# Mataric1.net
KiCad netlist of a schematic drawn in Altium Designer
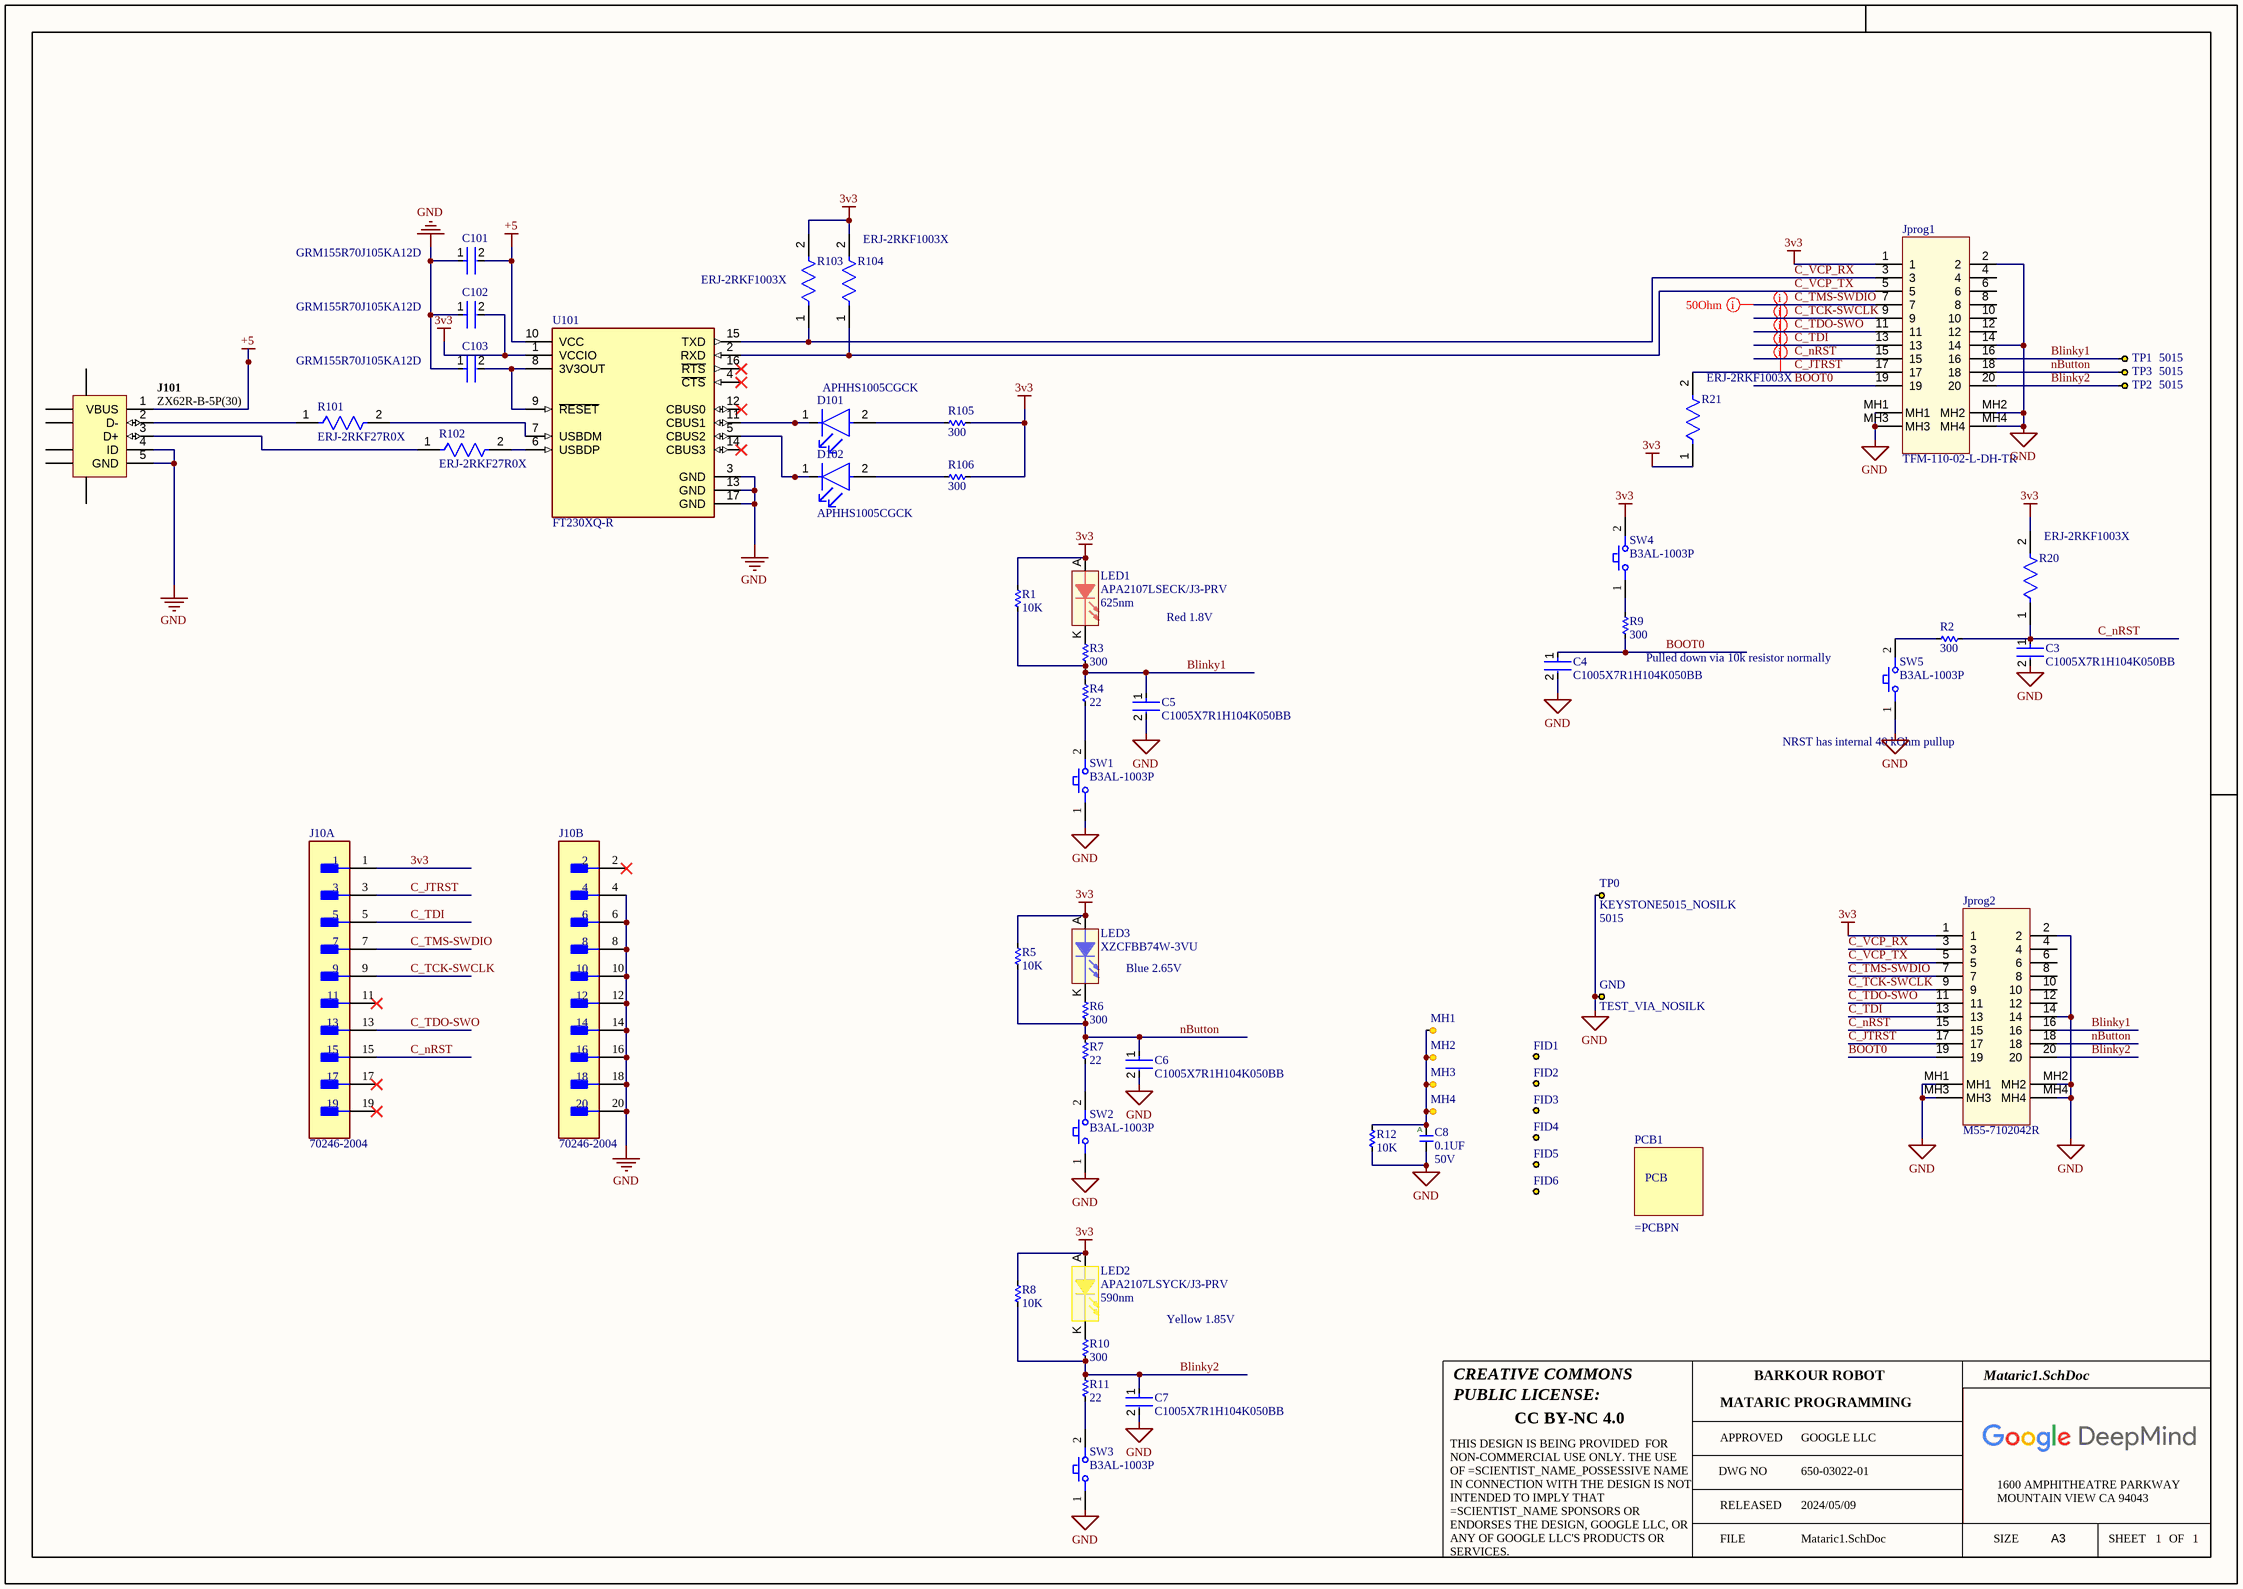
[diagram p0: Mataric1.SchDoc]

(export (version "E")
  (design (tool "Eeschema 10.0.6"))
  (components
    (comp (ref "C3")
      (value "C1005X7R1H104K050BB")
      (footprint "FP-C1005-050-0_05-IPC_C")
      (description "Multilayer Ceramic Capacitors 100nF ±10% 50V X7R SMD 0402")
      (fields (field (name "VOLTAGE") "50V") (field (name "TOLERANCE") "10%"))
      (libsource (lib "Altium Content Vault") (part "b4654b650e69147ec39a6b967a45e02"))
    )
    (comp (ref "C4")
      (value "C1005X7R1H104K050BB")
      (footprint "FP-C1005-050-0_05-IPC_C")
      (description "Multilayer Ceramic Capacitors 100nF ±10% 50V X7R SMD 0402")
      (fields (field (name "VOLTAGE") "50V") (field (name "TOLERANCE") "10%"))
      (libsource (lib "Altium Content Vault") (part "b4654b650e69147ec39a6b967a45e02"))
    )
    (comp (ref "C5")
      (value "C1005X7R1H104K050BB")
      (footprint "FP-C1005-050-0_05-IPC_C")
      (description "Multilayer Ceramic Capacitors 100nF ±10% 50V X7R SMD 0402")
      (fields (field (name "VOLTAGE") "50V") (field (name "TOLERANCE") "10%"))
      (libsource (lib "Altium Content Vault") (part "b4654b650e69147ec39a6b967a45e02"))
    )
    (comp (ref "C6")
      (value "C1005X7R1H104K050BB")
      (footprint "FP-C1005-050-0_05-IPC_C")
      (description "Multilayer Ceramic Capacitors 100nF ±10% 50V X7R SMD 0402")
      (fields (field (name "VOLTAGE") "50V") (field (name "TOLERANCE") "10%"))
      (libsource (lib "Altium Content Vault") (part "b4654b650e69147ec39a6b967a45e02"))
    )
    (comp (ref "C7")
      (value "C1005X7R1H104K050BB")
      (footprint "FP-C1005-050-0_05-IPC_C")
      (description "Multilayer Ceramic Capacitors 100nF ±10% 50V X7R SMD 0402")
      (fields (field (name "VOLTAGE") "50V") (field (name "TOLERANCE") "10%"))
      (libsource (lib "Altium Content Vault") (part "b4654b650e69147ec39a6b967a45e02"))
    )
    (comp (ref "C8")
      (value "0.1UF")
      (footprint "C0402")
      (description "CAP, CER, X7R, 0.1uF, 50V, 10%, 0402, AUTO GRADE")
      (fields (field (name "MFG") "TDK") (field (name "VOLTAGE") "50V") (field (name "TOLERANCE") "10%"))
      (libsource (lib "AltiumReleaseLibDB") (part "__Template_Cap_Auto"))
    )
    (comp (ref "C101")
      (value "GRM155R70J105KA12D")
      (footprint "FP-GRM155-0_05-MFG")
      (description "Chip Multilayer Ceramic Capacitors for General Purpose, 0402, 1.0uF, X7R, 15%, 10%, 6.3V")
      (fields (field (name "TOLERANCE") "10%"))
      (libsource (lib "Altium Content Vault") (part "02cd4be3c70576c341d710602a673aa"))
    )
    (comp (ref "C102")
      (value "GRM155R70J105KA12D")
      (footprint "FP-GRM155-0_05-MFG")
      (description "Chip Multilayer Ceramic Capacitors for General Purpose, 0402, 1.0uF, X7R, 15%, 10%, 6.3V")
      (fields (field (name "TOLERANCE") "10%"))
      (libsource (lib "Altium Content Vault") (part "02cd4be3c70576c341d710602a673aa"))
    )
    (comp (ref "C103")
      (value "GRM155R70J105KA12D")
      (footprint "FP-GRM155-0_05-MFG")
      (description "Chip Multilayer Ceramic Capacitors for General Purpose, 0402, 1.0uF, X7R, 15%, 10%, 6.3V")
      (fields (field (name "TOLERANCE") "10%"))
      (libsource (lib "Altium Content Vault") (part "02cd4be3c70576c341d710602a673aa"))
    )
    (comp (ref "D101")
      (value "APHHS1005CGCK")
      (footprint "FP-APHHS1005CGCK-MFG")
      (description "LED GREEN CLEAR CHIP SMD")
      (libsource (lib "Altium Content Vault") (part "8706943c75ba83719d021d2fdc84c58"))
    )
    (comp (ref "D102")
      (value "APHHS1005CGCK")
      (footprint "FP-APHHS1005CGCK-MFG")
      (description "LED GREEN CLEAR CHIP SMD")
      (libsource (lib "Altium Content Vault") (part "8706943c75ba83719d021d2fdc84c58"))
    )
    (comp (ref "FID1")
      (value "FIDUCIAL")
      (footprint "FIDUCIAL_1MM")
      (description "FIDUCIAL 1MM COPPER CIRCLE 3MM MASK PULLBACK")
      (fields (field (name "MFG") "_PCB Feature"))
      (libsource (lib "AltiumReleaseLibDB") (part "FIDUCIAL"))
    )
    (comp (ref "FID2")
      (value "FIDUCIAL")
      (footprint "FIDUCIAL_1MM")
      (description "FIDUCIAL 1MM COPPER CIRCLE 3MM MASK PULLBACK")
      (fields (field (name "MFG") "_PCB Feature"))
      (libsource (lib "AltiumReleaseLibDB") (part "FIDUCIAL"))
    )
    (comp (ref "FID3")
      (value "FIDUCIAL")
      (footprint "FIDUCIAL_1MM")
      (description "FIDUCIAL 1MM COPPER CIRCLE 3MM MASK PULLBACK")
      (fields (field (name "MFG") "_PCB Feature"))
      (libsource (lib "AltiumReleaseLibDB") (part "FIDUCIAL"))
    )
    (comp (ref "FID4")
      (value "FIDUCIAL")
      (footprint "FIDUCIAL_1MM")
      (description "FIDUCIAL 1MM COPPER CIRCLE 3MM MASK PULLBACK")
      (fields (field (name "MFG") "_PCB Feature"))
      (libsource (lib "AltiumReleaseLibDB") (part "FIDUCIAL"))
    )
    (comp (ref "FID5")
      (value "FIDUCIAL")
      (footprint "FIDUCIAL_1MM")
      (description "FIDUCIAL 1MM COPPER CIRCLE 3MM MASK PULLBACK")
      (fields (field (name "MFG") "_PCB Feature"))
      (libsource (lib "AltiumReleaseLibDB") (part "FIDUCIAL"))
    )
    (comp (ref "FID6")
      (value "FIDUCIAL")
      (footprint "FIDUCIAL_1MM")
      (description "FIDUCIAL 1MM COPPER CIRCLE 3MM MASK PULLBACK")
      (fields (field (name "MFG") "_PCB Feature"))
      (libsource (lib "AltiumReleaseLibDB") (part "FIDUCIAL"))
    )
    (comp (ref "GND")
      (value "TEST_VIA_NOSILK")
      (footprint "TP_VIA_31pad_15drill_NS")
      (description "TEST VIA, NO SILKSCREEN, 15 MIL DRILL, 31 MIL PAD")
      (fields (field (name "MFG") "_PCB Feature"))
      (libsource (lib "AltiumReleaseLibDB") (part "TEST_VIA_NOSILK"))
    )
    (comp (ref "J10")
      (value "70246-2004")
      (footprint "FP-70246-2004-MFG")
      (description "CONN HEADER VERT 20POS 2.54MM")
      (libsource (lib "Altium Content Vault") (part "3c9050f31bf3a235369f849c918cfe7"))
    )
    (comp (ref "J101")
      (value "ZX62R-B-5P(30)")
      (footprint "HIRO-ZX62R-B-5P_V")
      (description "Connector; USBMicro-B,Reverse type, SMT; 5 Position; Right Angle")
      (libsource (lib "Altium Content Vault") (part "HIRO-ZX62R-B-5P-5"))
    )
    (comp (ref "Jprog1")
      (value "~")
      (footprint "SAMTEC_TFM-110-02-L-DH")
      (description "CONN, HDR, SHRD, RA, 2x10, 1.27MM P, 6.02MM h, GOLD, TH")
      (fields (field (name "MFG") "Samtec Inc") (field (name "MFG P/N") "TFM-110-02-L-DH-TR"))
      (libsource (lib "AltiumReleaseLibDB") (part "__Template_Connector_2X10_4MH"))
    )
    (comp (ref "Jprog2")
      (value "M55-7102042R")
      (footprint "CON_M55-7102042R")
      (description "CONN HEADER SMD R/A 20POS 1.27MM")
      (fields (field (name "MFG") "Harwin Inc.") (field (name "MFG P/N") "M55-7102042R"))
      (libsource (lib "AltiumReleaseLibDB") (part "__Template_Connector_2X10_4MH"))
    )
    (comp (ref "LED1")
      (value "APA2107LSECK/J3-PRV")
      (footprint "LED_APA2106CGCK")
      (description "LED, RED, 640NM, INDEPENDENT, CLEAR, RA, SMD-2")
      (fields
        (field (name "MFG") "Kingbright")
        (field (name "COLOR / WAVELENGTH") "625nm")
        (field (name "Comment") "__Template_LED_RED_AK")
      )
      (libsource (lib "AltiumReleaseLibDB") (part "__Template_LED_RED_AK"))
    )
    (comp (ref "LED2")
      (value "APA2107LSYCK/J3-PRV")
      (footprint "LED_APA2106CGCK")
      (description "LED, YELLOW, 590NM, CLEAR, RA, SMD-2")
      (fields
        (field (name "MFG") "Kingbright")
        (field (name "COLOR / WAVELENGTH") "590nm")
        (field (name "Comment") "__Template_LED_YELLOW_AK")
      )
      (libsource (lib "AltiumReleaseLibDB") (part "__Template_LED_YELLOW_AK"))
    )
    (comp (ref "LED3")
      (value "XZCFBB74W-3VU")
      (footprint "LED_APA2106CGCK")
      (description "LED, BLUE, 465NM, INDEPENDENT, CLEAR, RA, SMD-2")
      (fields (field (name "MFG") "SunLED") (field (name "Comment") "__Template_LED_BLUE_AK"))
      (libsource (lib "AltiumReleaseLibDB") (part "__Template_LED_BLUE_AK"))
    )
    (comp (ref "MH1")
      (value "MH")
      (footprint "MH_1.6MM")
      (description "MOUNTING HOLE, M1.6, 4.0mm PAD")
      (libsource (lib "AltiumReleaseLibDB") (part "MH"))
    )
    (comp (ref "MH2")
      (value "MH")
      (footprint "MH_1.6MM")
      (description "MOUNTING HOLE, M1.6, 4.0mm PAD")
      (libsource (lib "AltiumReleaseLibDB") (part "MH"))
    )
    (comp (ref "MH3")
      (value "MH")
      (footprint "MH_1.6MM")
      (description "MOUNTING HOLE, M1.6, 4.0mm PAD")
      (libsource (lib "AltiumReleaseLibDB") (part "MH"))
    )
    (comp (ref "MH4")
      (value "MH")
      (footprint "MH_1.6MM")
      (description "MOUNTING HOLE, M1.6, 4.0mm PAD")
      (libsource (lib "AltiumReleaseLibDB") (part "MH"))
    )
    (comp (ref "PCB1")
      (value "651-PCB")
      (description "PCB")
      (libsource (lib "AltiumReleaseLibDB") (part "Label"))
    )
    (comp (ref "R1")
      (value "10K")
      (footprint "R0805")
      (description "RES, 10K, 1%, 1/8W, 0805")
      (fields (field (name "MFG") "YAGEO") (field (name "POWER") "1/8W"))
      (libsource (lib "AltiumReleaseLibDB") (part "__Template_Resistor"))
    )
    (comp (ref "R2")
      (value "300")
      (footprint "R0603")
      (description "Resistor, 300 Ohms, 0603, 0.1W, ±1%")
      (fields (field (name "MFG") "YAGEO") (field (name "POWER") "1/10W"))
      (libsource (lib "AltiumReleaseLibDB") (part "__Template_Resistor"))
    )
    (comp (ref "R3")
      (value "300")
      (footprint "R0603")
      (description "Resistor, 300 Ohms, 0603, 0.1W, ±1%")
      (fields (field (name "MFG") "YAGEO") (field (name "POWER") "1/10W"))
      (libsource (lib "AltiumReleaseLibDB") (part "__Template_Resistor"))
    )
    (comp (ref "R4")
      (value "22")
      (footprint "R0805")
      (description "Resistor, 22.0 Ohms, 0805, 0.125W, ±1%")
      (fields (field (name "MFG") "YAGEO") (field (name "POWER") "1/8W"))
      (libsource (lib "AltiumReleaseLibDB") (part "__Template_Resistor"))
    )
    (comp (ref "R5")
      (value "10K")
      (footprint "R0805")
      (description "RES, 10K, 1%, 1/8W, 0805")
      (fields (field (name "MFG") "YAGEO") (field (name "POWER") "1/8W"))
      (libsource (lib "AltiumReleaseLibDB") (part "__Template_Resistor"))
    )
    (comp (ref "R6")
      (value "300")
      (footprint "R0603")
      (description "Resistor, 300 Ohms, 0603, 0.1W, ±1%")
      (fields (field (name "MFG") "YAGEO") (field (name "POWER") "1/10W"))
      (libsource (lib "AltiumReleaseLibDB") (part "__Template_Resistor"))
    )
    (comp (ref "R7")
      (value "22")
      (footprint "R0805")
      (description "Resistor, 22.0 Ohms, 0805, 0.125W, ±1%")
      (fields (field (name "MFG") "YAGEO") (field (name "POWER") "1/8W"))
      (libsource (lib "AltiumReleaseLibDB") (part "__Template_Resistor"))
    )
    (comp (ref "R8")
      (value "10K")
      (footprint "R0805")
      (description "RES, 10K, 1%, 1/8W, 0805")
      (fields (field (name "MFG") "YAGEO") (field (name "POWER") "1/8W"))
      (libsource (lib "AltiumReleaseLibDB") (part "__Template_Resistor"))
    )
    (comp (ref "R9")
      (value "300")
      (footprint "R0603")
      (description "Resistor, 300 Ohms, 0603, 0.1W, ±1%")
      (fields (field (name "MFG") "YAGEO") (field (name "POWER") "1/10W"))
      (libsource (lib "AltiumReleaseLibDB") (part "__Template_Resistor"))
    )
    (comp (ref "R10")
      (value "300")
      (footprint "R0603")
      (description "Resistor, 300 Ohms, 0603, 0.1W, ±1%")
      (fields (field (name "MFG") "YAGEO") (field (name "POWER") "1/10W"))
      (libsource (lib "AltiumReleaseLibDB") (part "__Template_Resistor"))
    )
    (comp (ref "R11")
      (value "22")
      (footprint "R0805")
      (description "Resistor, 22.0 Ohms, 0805, 0.125W, ±1%")
      (fields (field (name "MFG") "YAGEO") (field (name "POWER") "1/8W"))
      (libsource (lib "AltiumReleaseLibDB") (part "__Template_Resistor"))
    )
    (comp (ref "R12")
      (value "10K")
      (footprint "R0805")
      (description "RES, 10K, 1%, 1/8W, 0805")
      (fields (field (name "MFG") "YAGEO") (field (name "POWER") "1/8W"))
      (libsource (lib "AltiumReleaseLibDB") (part "__Template_Resistor"))
    )
    (comp (ref "R20")
      (value "ERJ-2RKF1003X")
      (footprint "FP-ERJ2RK-IPC_C")
      (description "RES SMD 100K OHM 1% 1/10W 0402")
      (fields (field (name "TOLERANCE") "1%"))
      (libsource (lib "Altium Content Vault") (part "1029c3af85768c4190bb7ad29bc67b5"))
    )
    (comp (ref "R21")
      (value "ERJ-2RKF1003X")
      (footprint "FP-ERJ2RK-IPC_C")
      (description "RES SMD 100K OHM 1% 1/10W 0402")
      (fields (field (name "TOLERANCE") "1%"))
      (libsource (lib "Altium Content Vault") (part "1029c3af85768c4190bb7ad29bc67b5"))
    )
    (comp (ref "R101")
      (value "ERJ-2RKF27R0X")
      (footprint "FP-ERJ2R-IPC_B")
      (description "RES SMD 27 OHM 1% 1/10W 0402")
      (fields (field (name "TOLERANCE") "1%"))
      (libsource (lib "Altium Content Vault") (part "8db39607336c341a927600551d01821"))
    )
    (comp (ref "R102")
      (value "ERJ-2RKF27R0X")
      (footprint "FP-ERJ2R-IPC_B")
      (description "RES SMD 27 OHM 1% 1/10W 0402")
      (fields (field (name "TOLERANCE") "1%"))
      (libsource (lib "Altium Content Vault") (part "8db39607336c341a927600551d01821"))
    )
    (comp (ref "R103")
      (value "ERJ-2RKF1003X")
      (footprint "FP-ERJ2RK-IPC_C")
      (description "RES SMD 100K OHM 1% 1/10W 0402")
      (fields (field (name "TOLERANCE") "1%"))
      (libsource (lib "Altium Content Vault") (part "1029c3af85768c4190bb7ad29bc67b5"))
    )
    (comp (ref "R104")
      (value "ERJ-2RKF1003X")
      (footprint "FP-ERJ2RK-IPC_C")
      (description "RES SMD 100K OHM 1% 1/10W 0402")
      (fields (field (name "TOLERANCE") "1%"))
      (libsource (lib "Altium Content Vault") (part "1029c3af85768c4190bb7ad29bc67b5"))
    )
    (comp (ref "R105")
      (value "300")
      (footprint "R0603")
      (description "Resistor, 300 Ohms, 0603, 0.1W, ±1%")
      (fields (field (name "MFG") "YAGEO") (field (name "POWER") "1/10W"))
      (libsource (lib "AltiumReleaseLibDB") (part "__Template_Resistor"))
    )
    (comp (ref "R106")
      (value "300")
      (footprint "R0603")
      (description "Resistor, 300 Ohms, 0603, 0.1W, ±1%")
      (fields (field (name "MFG") "YAGEO") (field (name "POWER") "1/10W"))
      (libsource (lib "AltiumReleaseLibDB") (part "__Template_Resistor"))
    )
    (comp (ref "SW1")
      (value "B3AL-1003P")
      (footprint "FP-B3AL-1003P-MFG")
      (description "SWITCH TACTILE SPST-NO 0.05A 16V")
      (libsource (lib "Altium Content Vault") (part "69e8347f6a24c021ef43a914a4df441"))
    )
    (comp (ref "SW2")
      (value "B3AL-1003P")
      (footprint "FP-B3AL-1003P-MFG")
      (description "SWITCH TACTILE SPST-NO 0.05A 16V")
      (libsource (lib "Altium Content Vault") (part "69e8347f6a24c021ef43a914a4df441"))
    )
    (comp (ref "SW3")
      (value "B3AL-1003P")
      (footprint "FP-B3AL-1003P-MFG")
      (description "SWITCH TACTILE SPST-NO 0.05A 16V")
      (libsource (lib "Altium Content Vault") (part "69e8347f6a24c021ef43a914a4df441"))
    )
    (comp (ref "SW4")
      (value "B3AL-1003P")
      (footprint "FP-B3AL-1003P-MFG")
      (description "SWITCH TACTILE SPST-NO 0.05A 16V")
      (libsource (lib "Altium Content Vault") (part "69e8347f6a24c021ef43a914a4df441"))
    )
    (comp (ref "SW5")
      (value "B3AL-1003P")
      (footprint "FP-B3AL-1003P-MFG")
      (description "SWITCH TACTILE SPST-NO 0.05A 16V")
      (libsource (lib "Altium Content Vault") (part "69e8347f6a24c021ef43a914a4df441"))
    )
    (comp (ref "TP0")
      (value "KEYSTONE5015_NOSILK")
      (footprint "KEYSTONE_5015_NS")
      (description "HW, TEST POINT, NO SILKSCREEN, PC MINIATURE, 0.25mm T, 1.52mm HEIGHT, SILVER PLATING, SMT")
      (fields (field (name "MFG") "Keystone Electronics Corp.") (field (name "MFG P/N") "5015"))
      (libsource (lib "AltiumReleaseLibDB") (part "TEST_KEYSTONE5015_NOSILK"))
    )
    (comp (ref "TP1")
      (value "KEYSTONE5015_NOSILK")
      (footprint "KEYSTONE_5015_NS")
      (description "HW, TEST POINT, NO SILKSCREEN, PC MINIATURE, 0.25mm T, 1.52mm HEIGHT, SILVER PLATING, SMT")
      (fields (field (name "MFG") "Keystone Electronics Corp.") (field (name "MFG P/N") "5015"))
      (libsource (lib "AltiumReleaseLibDB") (part "TEST_KEYSTONE5015_NOSILK"))
    )
    (comp (ref "TP2")
      (value "KEYSTONE5015_NOSILK")
      (footprint "KEYSTONE_5015_NS")
      (description "HW, TEST POINT, NO SILKSCREEN, PC MINIATURE, 0.25mm T, 1.52mm HEIGHT, SILVER PLATING, SMT")
      (fields (field (name "MFG") "Keystone Electronics Corp.") (field (name "MFG P/N") "5015"))
      (libsource (lib "AltiumReleaseLibDB") (part "TEST_KEYSTONE5015_NOSILK"))
    )
    (comp (ref "TP3")
      (value "KEYSTONE5015_NOSILK")
      (footprint "KEYSTONE_5015_NS")
      (description "HW, TEST POINT, NO SILKSCREEN, PC MINIATURE, 0.25mm T, 1.52mm HEIGHT, SILVER PLATING, SMT")
      (fields (field (name "MFG") "Keystone Electronics Corp.") (field (name "MFG P/N") "5015"))
      (libsource (lib "AltiumReleaseLibDB") (part "TEST_KEYSTONE5015_NOSILK"))
    )
    (comp (ref "U101")
      (value "FT230XQ-R")
      (footprint "FP-QFN-16-MFG")
      (description "IC USB SERIAL BASIC UART 16QFN")
      (libsource (lib "Altium Content Vault") (part "29d2eb9587eff32afae5da052de4085"))
    )
  )
  (nets
    (net (code "1") (name "+5") (class "Default")
      (node (ref "C101") (pin "2") (pinfunction "2_2") (pintype "passive"))
      (node (ref "J101") (pin "1") (pinfunction "VBUS_1") (pintype "power_in"))
      (node (ref "U101") (pin "10") (pinfunction "VCC_10") (pintype "power_in"))
    )
    (net (code "2") (name "/BOOT0") (class "Default")
      (node (ref "C4") (pin "1") (pinfunction "1_1") (pintype "passive"))
      (node (ref "Jprog1") (pin "19") (pinfunction "19_19") (pintype "passive"))
      (node (ref "Jprog2") (pin "19") (pinfunction "19_19") (pintype "passive"))
      (node (ref "R9") (pin "1") (pintype "passive"))
    )
    (net (code "3") (name "/Blinky1") (class "Default")
      (node (ref "C5") (pin "1") (pinfunction "1_1") (pintype "passive"))
      (node (ref "Jprog1") (pin "16") (pinfunction "16_16") (pintype "passive"))
      (node (ref "Jprog2") (pin "16") (pinfunction "16_16") (pintype "passive"))
      (node (ref "R1") (pin "1") (pintype "passive"))
      (node (ref "R3") (pin "1") (pintype "passive"))
      (node (ref "R4") (pin "2") (pintype "passive"))
      (node (ref "TP1") (pin "1") (pintype "passive"))
    )
    (net (code "4") (name "/Blinky2") (class "Default")
      (node (ref "C7") (pin "1") (pinfunction "1_1") (pintype "passive"))
      (node (ref "Jprog1") (pin "20") (pinfunction "20_20") (pintype "passive"))
      (node (ref "Jprog2") (pin "20") (pinfunction "20_20") (pintype "passive"))
      (node (ref "R10") (pin "1") (pintype "passive"))
      (node (ref "R11") (pin "2") (pintype "passive"))
      (node (ref "R8") (pin "1") (pintype "passive"))
      (node (ref "TP2") (pin "1") (pintype "passive"))
    )
    (net (code "5") (name "/C_JTRST") (class "Default")
      (node (ref "J10") (pin "3") (pinfunction "3_3") (pintype "passive"))
      (node (ref "Jprog1") (pin "17") (pinfunction "17_17") (pintype "passive"))
      (node (ref "Jprog2") (pin "17") (pinfunction "17_17") (pintype "passive"))
      (node (ref "R21") (pin "2") (pinfunction "2_2") (pintype "passive"))
    )
    (net (code "6") (name "/C_TCK-SWCLK") (class "Default")
      (node (ref "J10") (pin "9") (pinfunction "9_9") (pintype "passive"))
      (node (ref "Jprog1") (pin "9") (pinfunction "9_9") (pintype "passive"))
      (node (ref "Jprog2") (pin "9") (pinfunction "9_9") (pintype "passive"))
    )
    (net (code "7") (name "/C_TDI") (class "Default")
      (node (ref "J10") (pin "5") (pinfunction "5_5") (pintype "passive"))
      (node (ref "Jprog1") (pin "13") (pinfunction "13_13") (pintype "passive"))
      (node (ref "Jprog2") (pin "13") (pinfunction "13_13") (pintype "passive"))
    )
    (net (code "8") (name "/C_TDO-SWO") (class "Default")
      (node (ref "J10") (pin "13") (pinfunction "13_13") (pintype "passive"))
      (node (ref "Jprog1") (pin "11") (pinfunction "11_11") (pintype "passive"))
      (node (ref "Jprog2") (pin "11") (pinfunction "11_11") (pintype "passive"))
    )
    (net (code "9") (name "/C_TMS-SWDIO") (class "Default")
      (node (ref "J10") (pin "7") (pinfunction "7_7") (pintype "passive"))
      (node (ref "Jprog1") (pin "7") (pinfunction "7_7") (pintype "passive"))
      (node (ref "Jprog2") (pin "7") (pinfunction "7_7") (pintype "passive"))
    )
    (net (code "10") (name "/C_VCP_RX") (class "Default")
      (node (ref "Jprog1") (pin "3") (pinfunction "3_3") (pintype "passive"))
      (node (ref "Jprog2") (pin "3") (pinfunction "3_3") (pintype "passive"))
      (node (ref "R103") (pin "1") (pinfunction "1_1") (pintype "passive"))
      (node (ref "U101") (pin "15") (pinfunction "TXD_15") (pintype "output"))
    )
    (net (code "11") (name "/C_VCP_TX") (class "Default")
      (node (ref "Jprog1") (pin "5") (pinfunction "5_5") (pintype "passive"))
      (node (ref "Jprog2") (pin "5") (pinfunction "5_5") (pintype "passive"))
      (node (ref "R104") (pin "1") (pinfunction "1_1") (pintype "passive"))
      (node (ref "U101") (pin "2") (pinfunction "RXD_2") (pintype "input"))
    )
    (net (code "12") (name "/C_nRST") (class "Default")
      (node (ref "C3") (pin "1") (pinfunction "1_1") (pintype "passive"))
      (node (ref "J10") (pin "15") (pinfunction "15_15") (pintype "passive"))
      (node (ref "Jprog1") (pin "15") (pinfunction "15_15") (pintype "passive"))
      (node (ref "Jprog2") (pin "15") (pinfunction "15_15") (pintype "passive"))
      (node (ref "R2") (pin "1") (pintype "passive"))
      (node (ref "R20") (pin "1") (pinfunction "1_1") (pintype "passive"))
    )
    (net (code "13") (name "/nButton") (class "Default")
      (node (ref "C6") (pin "1") (pinfunction "1_1") (pintype "passive"))
      (node (ref "Jprog1") (pin "18") (pinfunction "18_18") (pintype "passive"))
      (node (ref "Jprog2") (pin "18") (pinfunction "18_18") (pintype "passive"))
      (node (ref "R5") (pin "1") (pintype "passive"))
      (node (ref "R6") (pin "1") (pintype "passive"))
      (node (ref "R7") (pin "2") (pintype "passive"))
      (node (ref "TP3") (pin "1") (pintype "passive"))
    )
    (net (code "14") (name "3v3") (class "Default")
      (node (ref "C102") (pin "2") (pinfunction "2_2") (pintype "passive"))
      (node (ref "J10") (pin "1") (pinfunction "1_1") (pintype "passive"))
      (node (ref "Jprog1") (pin "1") (pinfunction "1_1") (pintype "passive"))
      (node (ref "Jprog2") (pin "1") (pinfunction "1_1") (pintype "passive"))
      (node (ref "LED1") (pin "A") (pinfunction "A_A") (pintype "passive"))
      (node (ref "LED2") (pin "A") (pinfunction "A_A") (pintype "passive"))
      (node (ref "LED3") (pin "A") (pinfunction "A_A") (pintype "passive"))
      (node (ref "R1") (pin "2") (pintype "passive"))
      (node (ref "R103") (pin "2") (pinfunction "2_2") (pintype "passive"))
      (node (ref "R104") (pin "2") (pinfunction "2_2") (pintype "passive"))
      (node (ref "R105") (pin "1") (pintype "passive"))
      (node (ref "R106") (pin "1") (pintype "passive"))
      (node (ref "R20") (pin "2") (pinfunction "2_2") (pintype "passive"))
      (node (ref "R21") (pin "1") (pinfunction "1_1") (pintype "passive"))
      (node (ref "R5") (pin "2") (pintype "passive"))
      (node (ref "R8") (pin "2") (pintype "passive"))
      (node (ref "SW4") (pin "2") (pinfunction "2_2") (pintype "passive"))
      (node (ref "U101") (pin "1") (pinfunction "VCCIO_1") (pintype "power_in"))
    )
    (net (code "15") (name "GND") (class "Default")
      (node (ref "C101") (pin "1") (pinfunction "1_1") (pintype "passive"))
      (node (ref "C102") (pin "1") (pinfunction "1_1") (pintype "passive"))
      (node (ref "C103") (pin "1") (pinfunction "1_1") (pintype "passive"))
      (node (ref "C3") (pin "2") (pinfunction "2_2") (pintype "passive"))
      (node (ref "C4") (pin "2") (pinfunction "2_2") (pintype "passive"))
      (node (ref "C5") (pin "2") (pinfunction "2_2") (pintype "passive"))
      (node (ref "C6") (pin "2") (pinfunction "2_2") (pintype "passive"))
      (node (ref "C7") (pin "2") (pinfunction "2_2") (pintype "passive"))
      (node (ref "C8") (pin "2") (pintype "passive"))
      (node (ref "GND") (pin "1") (pintype "passive"))
      (node (ref "J10") (pin "10") (pinfunction "10_10") (pintype "passive"))
      (node (ref "J10") (pin "12") (pinfunction "12_12") (pintype "passive"))
      (node (ref "J10") (pin "14") (pinfunction "14_14") (pintype "passive"))
      (node (ref "J10") (pin "16") (pinfunction "16_16") (pintype "passive"))
      (node (ref "J10") (pin "18") (pinfunction "18_18") (pintype "passive"))
      (node (ref "J10") (pin "20") (pinfunction "20_20") (pintype "passive"))
      (node (ref "J10") (pin "4") (pinfunction "4_4") (pintype "passive"))
      (node (ref "J10") (pin "6") (pinfunction "6_6") (pintype "passive"))
      (node (ref "J10") (pin "8") (pinfunction "8_8") (pintype "passive"))
      (node (ref "J101") (pin "4") (pinfunction "ID_4") (pintype "passive"))
      (node (ref "J101") (pin "5") (pinfunction "GND_5") (pintype "power_in"))
      (node (ref "Jprog1") (pin "14") (pinfunction "14_14") (pintype "passive"))
      (node (ref "Jprog1") (pin "2") (pinfunction "2_2") (pintype "passive"))
      (node (ref "Jprog1") (pin "MH1") (pinfunction "MH1_MH1") (pintype "passive"))
      (node (ref "Jprog1") (pin "MH2") (pinfunction "MH2_MH2") (pintype "passive"))
      (node (ref "Jprog1") (pin "MH3") (pinfunction "MH3_MH3") (pintype "passive"))
      (node (ref "Jprog1") (pin "MH4") (pinfunction "MH4_MH4") (pintype "passive"))
      (node (ref "Jprog2") (pin "14") (pinfunction "14_14") (pintype "passive"))
      (node (ref "Jprog2") (pin "2") (pinfunction "2_2") (pintype "passive"))
      (node (ref "Jprog2") (pin "MH1") (pinfunction "MH1_MH1") (pintype "passive"))
      (node (ref "Jprog2") (pin "MH2") (pinfunction "MH2_MH2") (pintype "passive"))
      (node (ref "Jprog2") (pin "MH3") (pinfunction "MH3_MH3") (pintype "passive"))
      (node (ref "Jprog2") (pin "MH4") (pinfunction "MH4_MH4") (pintype "passive"))
      (node (ref "R12") (pin "1") (pintype "passive"))
      (node (ref "SW1") (pin "1") (pinfunction "1_1") (pintype "passive"))
      (node (ref "SW2") (pin "1") (pinfunction "1_1") (pintype "passive"))
      (node (ref "SW3") (pin "1") (pinfunction "1_1") (pintype "passive"))
      (node (ref "SW5") (pin "1") (pinfunction "1_1") (pintype "passive"))
      (node (ref "TP0") (pin "1") (pintype "passive"))
      (node (ref "U101") (pin "13") (pinfunction "GND_13") (pintype "power_in"))
      (node (ref "U101") (pin "17") (pinfunction "GND_17") (pintype "power_in"))
      (node (ref "U101") (pin "3") (pinfunction "GND_3") (pintype "power_in"))
    )
    (net (code "16") (name "Net-(C8-Pad1)") (class "Default")
      (node (ref "C8") (pin "1") (pintype "passive"))
      (node (ref "MH1") (pin "1") (pintype "passive"))
      (node (ref "MH2") (pin "1") (pintype "passive"))
      (node (ref "MH3") (pin "1") (pintype "passive"))
      (node (ref "MH4") (pin "1") (pintype "passive"))
      (node (ref "R12") (pin "2") (pintype "passive"))
    )
    (net (code "17") (name "Net-(D101-A)") (class "Default")
      (node (ref "D101") (pin "2") (pinfunction "A_2") (pintype "passive"))
      (node (ref "R105") (pin "2") (pintype "passive"))
    )
    (net (code "18") (name "Net-(D101-C)") (class "Default")
      (node (ref "D101") (pin "1") (pinfunction "C_1") (pintype "passive"))
      (node (ref "U101") (pin "11") (pinfunction "CBUS1_11") (pintype "bidirectional"))
    )
    (net (code "19") (name "Net-(D102-A)") (class "Default")
      (node (ref "D102") (pin "2") (pinfunction "A_2") (pintype "passive"))
      (node (ref "R106") (pin "2") (pintype "passive"))
    )
    (net (code "20") (name "Net-(D102-C)") (class "Default")
      (node (ref "D102") (pin "1") (pinfunction "C_1") (pintype "passive"))
      (node (ref "U101") (pin "5") (pinfunction "CBUS2_5") (pintype "bidirectional"))
    )
    (net (code "21") (name "Net-(J101-D+)") (class "Default")
      (node (ref "J101") (pin "3") (pinfunction "D+_3") (pintype "bidirectional"))
      (node (ref "R102") (pin "1") (pinfunction "1_1") (pintype "passive"))
    )
    (net (code "22") (name "Net-(J101-D-)") (class "Default")
      (node (ref "J101") (pin "2") (pinfunction "D-_2") (pintype "bidirectional"))
      (node (ref "R101") (pin "1") (pinfunction "1_1") (pintype "passive"))
    )
    (net (code "23") (name "Net-(LED1-PadK)") (class "Default")
      (node (ref "LED1") (pin "K") (pinfunction "K_K") (pintype "passive"))
      (node (ref "R3") (pin "2") (pintype "passive"))
    )
    (net (code "24") (name "Net-(LED2-PadK)") (class "Default")
      (node (ref "LED2") (pin "K") (pinfunction "K_K") (pintype "passive"))
      (node (ref "R10") (pin "2") (pintype "passive"))
    )
    (net (code "25") (name "Net-(LED3-PadK)") (class "Default")
      (node (ref "LED3") (pin "K") (pinfunction "K_K") (pintype "passive"))
      (node (ref "R6") (pin "2") (pintype "passive"))
    )
    (net (code "26") (name "Net-(R2-Pad2)") (class "Default")
      (node (ref "R2") (pin "2") (pintype "passive"))
      (node (ref "SW5") (pin "2") (pinfunction "2_2") (pintype "passive"))
    )
    (net (code "27") (name "Net-(R4-Pad1)") (class "Default")
      (node (ref "R4") (pin "1") (pintype "passive"))
      (node (ref "SW1") (pin "2") (pinfunction "2_2") (pintype "passive"))
    )
    (net (code "28") (name "Net-(R7-Pad1)") (class "Default")
      (node (ref "R7") (pin "1") (pintype "passive"))
      (node (ref "SW2") (pin "2") (pinfunction "2_2") (pintype "passive"))
    )
    (net (code "29") (name "Net-(R9-Pad2)") (class "Default")
      (node (ref "R9") (pin "2") (pintype "passive"))
      (node (ref "SW4") (pin "1") (pinfunction "1_1") (pintype "passive"))
    )
    (net (code "30") (name "Net-(R11-Pad1)") (class "Default")
      (node (ref "R11") (pin "1") (pintype "passive"))
      (node (ref "SW3") (pin "2") (pinfunction "2_2") (pintype "passive"))
    )
    (net (code "31") (name "Net-(U101-3V3OUT)") (class "Default")
      (node (ref "C103") (pin "2") (pinfunction "2_2") (pintype "passive"))
      (node (ref "U101") (pin "8") (pinfunction "3V3OUT_8") (pintype "power_in"))
      (node (ref "U101") (pin "9") (pinfunction "~{RESET}_9") (pintype "input"))
    )
    (net (code "32") (name "Net-(U101-USBDM)") (class "Default")
      (node (ref "R101") (pin "2") (pinfunction "2_2") (pintype "passive"))
      (node (ref "U101") (pin "7") (pinfunction "USBDM_7") (pintype "input"))
    )
    (net (code "33") (name "Net-(U101-USBDP)") (class "Default")
      (node (ref "R102") (pin "2") (pinfunction "2_2") (pintype "passive"))
      (node (ref "U101") (pin "6") (pinfunction "USBDP_6") (pintype "input"))
    )
    (net (code "34") (name "unconnected-(J10-Pad2)") (class "Default")
      (node (ref "J10") (pin "2") (pinfunction "2_2") (pintype "passive+no_connect"))
    )
    (net (code "35") (name "unconnected-(J10-Pad11)") (class "Default")
      (node (ref "J10") (pin "11") (pinfunction "11_11") (pintype "passive+no_connect"))
    )
    (net (code "36") (name "unconnected-(J10-Pad17)") (class "Default")
      (node (ref "J10") (pin "17") (pinfunction "17_17") (pintype "passive+no_connect"))
    )
    (net (code "37") (name "unconnected-(J10-Pad19)") (class "Default")
      (node (ref "J10") (pin "19") (pinfunction "19_19") (pintype "passive+no_connect"))
    )
    (net (code "38") (name "unconnected-(J101-SHLD-Pad6)") (class "Default")
      (node (ref "J101") (pin "6") (pinfunction "SHLD_6") (pintype "passive"))
    )
    (net (code "39") (name "unconnected-(J101-SHLD-Pad7)") (class "Default")
      (node (ref "J101") (pin "7") (pinfunction "SHLD_7") (pintype "passive"))
    )
    (net (code "40") (name "unconnected-(J101-SHLD-Pad8)") (class "Default")
      (node (ref "J101") (pin "8") (pinfunction "SHLD_8") (pintype "passive"))
    )
    (net (code "41") (name "unconnected-(J101-SHLD-Pad9)") (class "Default")
      (node (ref "J101") (pin "9") (pinfunction "SHLD_9") (pintype "passive"))
    )
    (net (code "42") (name "unconnected-(J101-SHLD-Pad10)") (class "Default")
      (node (ref "J101") (pin "10") (pinfunction "SHLD_10") (pintype "passive"))
    )
    (net (code "43") (name "unconnected-(J101-SHLD-Pad11)") (class "Default")
      (node (ref "J101") (pin "11") (pinfunction "SHLD_11") (pintype "passive"))
    )
    (net (code "44") (name "unconnected-(Jprog1-Pad4)") (class "Default")
      (node (ref "Jprog1") (pin "4") (pinfunction "4_4") (pintype "passive"))
    )
    (net (code "45") (name "unconnected-(Jprog1-Pad6)") (class "Default")
      (node (ref "Jprog1") (pin "6") (pinfunction "6_6") (pintype "passive"))
    )
    (net (code "46") (name "unconnected-(Jprog1-Pad8)") (class "Default")
      (node (ref "Jprog1") (pin "8") (pinfunction "8_8") (pintype "passive"))
    )
    (net (code "47") (name "unconnected-(Jprog1-Pad10)") (class "Default")
      (node (ref "Jprog1") (pin "10") (pinfunction "10_10") (pintype "passive"))
    )
    (net (code "48") (name "unconnected-(Jprog1-Pad12)") (class "Default")
      (node (ref "Jprog1") (pin "12") (pinfunction "12_12") (pintype "passive"))
    )
    (net (code "49") (name "unconnected-(Jprog2-Pad4)") (class "Default")
      (node (ref "Jprog2") (pin "4") (pinfunction "4_4") (pintype "passive"))
    )
    (net (code "50") (name "unconnected-(Jprog2-Pad6)") (class "Default")
      (node (ref "Jprog2") (pin "6") (pinfunction "6_6") (pintype "passive"))
    )
    (net (code "51") (name "unconnected-(Jprog2-Pad8)") (class "Default")
      (node (ref "Jprog2") (pin "8") (pinfunction "8_8") (pintype "passive"))
    )
    (net (code "52") (name "unconnected-(Jprog2-Pad10)") (class "Default")
      (node (ref "Jprog2") (pin "10") (pinfunction "10_10") (pintype "passive"))
    )
    (net (code "53") (name "unconnected-(Jprog2-Pad12)") (class "Default")
      (node (ref "Jprog2") (pin "12") (pinfunction "12_12") (pintype "passive"))
    )
    (net (code "54") (name "unconnected-(U101-CBUS0-Pad12)") (class "Default")
      (node (ref "U101") (pin "12") (pinfunction "CBUS0_12") (pintype "bidirectional+no_connect"))
    )
    (net (code "55") (name "unconnected-(U101-CBUS3-Pad14)") (class "Default")
      (node (ref "U101") (pin "14") (pinfunction "CBUS3_14") (pintype "bidirectional+no_connect"))
    )
    (net (code "56") (name "unconnected-(U101-~{CTS}-Pad4)") (class "Default")
      (node (ref "U101") (pin "4") (pinfunction "~{CTS}_4") (pintype "input+no_connect"))
    )
    (net (code "57") (name "unconnected-(U101-~{RTS}-Pad16)") (class "Default")
      (node (ref "U101") (pin "16") (pinfunction "~{RTS}_16") (pintype "output+no_connect"))
    )
  )
)
